# UI.net
KiCad netlist of a schematic drawn in Altium Designer
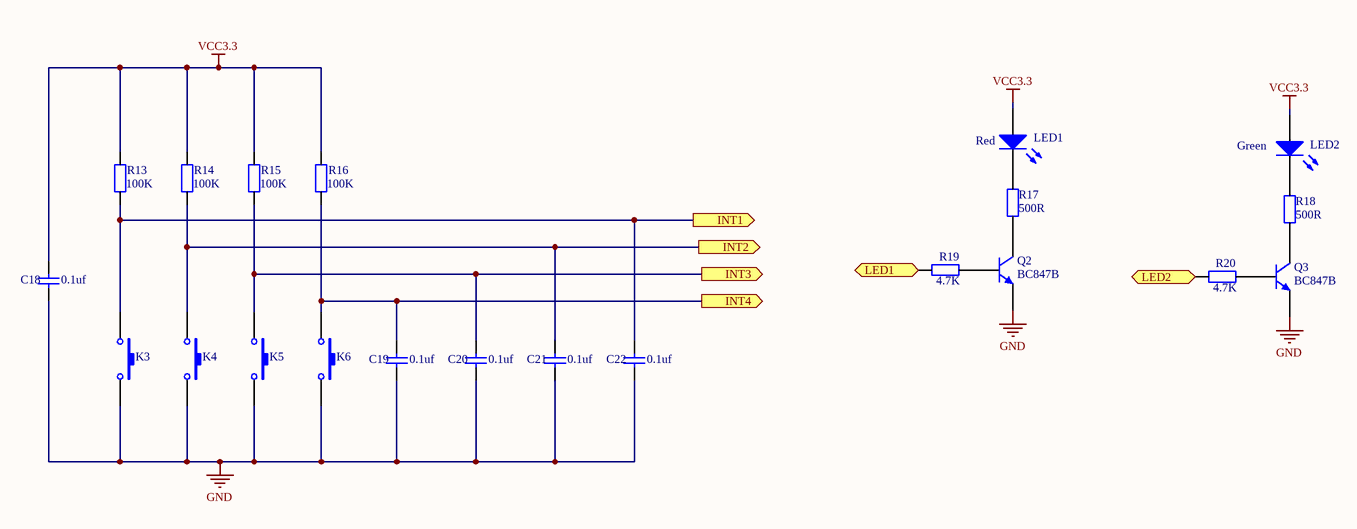
[diagram p0: UI.SchDoc]

(export (version "E")
  (design (tool "Eeschema 10.0.6"))
  (components
    (comp (ref "C18")
      (value "0.1uf")
      (footprint "0603")
      (fields (field (name "Comment") "Capacitor-0603"))
      (libsource (lib "原理图库") (part "Capacitor-0603"))
    )
    (comp (ref "C19")
      (value "0.1uf")
      (footprint "0603")
      (fields (field (name "Comment") "Capacitor-0603"))
      (libsource (lib "原理图库") (part "Capacitor-0603"))
    )
    (comp (ref "C20")
      (value "0.1uf")
      (footprint "0603")
      (fields (field (name "Comment") "Capacitor-0603"))
      (libsource (lib "原理图库") (part "Capacitor-0603"))
    )
    (comp (ref "C21")
      (value "0.1uf")
      (footprint "0603")
      (fields (field (name "Comment") "Capacitor-0603"))
      (libsource (lib "原理图库") (part "Capacitor-0603"))
    )
    (comp (ref "C22")
      (value "0.1uf")
      (footprint "0603")
      (fields (field (name "Comment") "Capacitor-0603"))
      (libsource (lib "原理图库") (part "Capacitor-0603"))
    )
    (comp (ref "K3") (value "按键") (footprint "mini按键") (libsource (lib "原理图库") (part "按键")))
    (comp (ref "K4") (value "按键") (footprint "mini按键") (libsource (lib "原理图库") (part "按键")))
    (comp (ref "K5") (value "按键") (footprint "mini按键") (libsource (lib "原理图库") (part "按键")))
    (comp (ref "K6") (value "按键") (footprint "mini按键") (libsource (lib "原理图库") (part "按键")))
    (comp (ref "LED1")
      (value "LED")
      (footprint "外插小灯")
      (fields (field (name "COLOR") "Red"))
      (libsource (lib "原理图库") (part "LED"))
    )
    (comp (ref "LED2")
      (value "LED")
      (footprint "外插小灯")
      (fields (field (name "COLOR") "Green"))
      (libsource (lib "原理图库") (part "LED"))
    )
    (comp (ref "Q2")
      (value "BC847")
      (footprint "BC847B")
      (fields (field (name "NAME") "BC847B"))
      (libsource (lib "原理图库") (part "BC847"))
    )
    (comp (ref "Q3")
      (value "BC847")
      (footprint "BC847B")
      (fields (field (name "NAME") "BC847B"))
      (libsource (lib "原理图库") (part "BC847"))
    )
    (comp (ref "R13")
      (value "100K")
      (footprint "0603")
      (fields (field (name "Comment") "Resistor-0603"))
      (libsource (lib "原理图库") (part "Resistor-0603"))
    )
    (comp (ref "R14")
      (value "100K")
      (footprint "0603")
      (fields (field (name "Comment") "Resistor-0603"))
      (libsource (lib "原理图库") (part "Resistor-0603"))
    )
    (comp (ref "R15")
      (value "100K")
      (footprint "0603")
      (fields (field (name "Comment") "Resistor-0603"))
      (libsource (lib "原理图库") (part "Resistor-0603"))
    )
    (comp (ref "R16")
      (value "100K")
      (footprint "0603")
      (fields (field (name "Comment") "Resistor-0603"))
      (libsource (lib "原理图库") (part "Resistor-0603"))
    )
    (comp (ref "R17")
      (value "500R")
      (footprint "0603")
      (fields (field (name "Comment") "Resistor-0603"))
      (libsource (lib "原理图库") (part "Resistor-0603"))
    )
    (comp (ref "R18")
      (value "500R")
      (footprint "0603")
      (fields (field (name "Comment") "Resistor-0603"))
      (libsource (lib "原理图库") (part "Resistor-0603"))
    )
    (comp (ref "R19")
      (value "4.7K")
      (footprint "0603")
      (fields (field (name "Comment") "Resistor-0603"))
      (libsource (lib "") (part "Resistor-0603_1"))
    )
    (comp (ref "R20")
      (value "4.7K")
      (footprint "0603")
      (fields (field (name "Comment") "Resistor-0603"))
      (libsource (lib "") (part "Resistor-0603_1"))
    )
  )
  (nets
    (net (code "1") (name "/INT1") (class "Default")
      (node (ref "C22") (pin "2") (pinfunction "2_2") (pintype "passive"))
      (node (ref "K3") (pin "1") (pinfunction "1_1") (pintype "passive"))
      (node (ref "R13") (pin "1") (pinfunction "1_1") (pintype "passive"))
    )
    (net (code "2") (name "/INT2") (class "Default")
      (node (ref "C21") (pin "2") (pinfunction "2_2") (pintype "passive"))
      (node (ref "K4") (pin "1") (pinfunction "1_1") (pintype "passive"))
      (node (ref "R14") (pin "1") (pinfunction "1_1") (pintype "passive"))
    )
    (net (code "3") (name "/INT3") (class "Default")
      (node (ref "C20") (pin "2") (pinfunction "2_2") (pintype "passive"))
      (node (ref "K5") (pin "1") (pinfunction "1_1") (pintype "passive"))
      (node (ref "R15") (pin "1") (pinfunction "1_1") (pintype "passive"))
    )
    (net (code "4") (name "/INT4") (class "Default")
      (node (ref "C19") (pin "2") (pinfunction "2_2") (pintype "passive"))
      (node (ref "K6") (pin "1") (pinfunction "1_1") (pintype "passive"))
      (node (ref "R16") (pin "1") (pinfunction "1_1") (pintype "passive"))
    )
    (net (code "5") (name "/LED1") (class "Default")
      (node (ref "R19") (pin "2") (pinfunction "2_2") (pintype "passive"))
    )
    (net (code "6") (name "/LED2") (class "Default")
      (node (ref "R20") (pin "2") (pinfunction "2_2") (pintype "passive"))
    )
    (net (code "7") (name "GND") (class "Default")
      (node (ref "C18") (pin "1") (pinfunction "1_1") (pintype "passive"))
      (node (ref "C19") (pin "1") (pinfunction "1_1") (pintype "passive"))
      (node (ref "C20") (pin "1") (pinfunction "1_1") (pintype "passive"))
      (node (ref "C21") (pin "1") (pinfunction "1_1") (pintype "passive"))
      (node (ref "C22") (pin "1") (pinfunction "1_1") (pintype "passive"))
      (node (ref "K3") (pin "2") (pinfunction "2_2") (pintype "passive"))
      (node (ref "K4") (pin "2") (pinfunction "2_2") (pintype "passive"))
      (node (ref "K5") (pin "2") (pinfunction "2_2") (pintype "passive"))
      (node (ref "K6") (pin "2") (pinfunction "2_2") (pintype "passive"))
      (node (ref "Q2") (pin "1") (pinfunction "E_1") (pintype "passive"))
      (node (ref "Q3") (pin "1") (pinfunction "E_1") (pintype "passive"))
    )
    (net (code "8") (name "Net-(LED1-Pad2)") (class "Default")
      (node (ref "LED1") (pin "2") (pinfunction "2_2") (pintype "passive"))
      (node (ref "R17") (pin "2") (pinfunction "2_2") (pintype "passive"))
    )
    (net (code "9") (name "Net-(LED2-Pad2)") (class "Default")
      (node (ref "LED2") (pin "2") (pinfunction "2_2") (pintype "passive"))
      (node (ref "R18") (pin "2") (pinfunction "2_2") (pintype "passive"))
    )
    (net (code "10") (name "Net-(Q2-B)") (class "Default")
      (node (ref "Q2") (pin "2") (pinfunction "B_2") (pintype "passive"))
      (node (ref "R19") (pin "1") (pinfunction "1_1") (pintype "passive"))
    )
    (net (code "11") (name "Net-(Q2-C)") (class "Default")
      (node (ref "Q2") (pin "3") (pinfunction "C_3") (pintype "passive"))
      (node (ref "R17") (pin "1") (pinfunction "1_1") (pintype "passive"))
    )
    (net (code "12") (name "Net-(Q3-B)") (class "Default")
      (node (ref "Q3") (pin "2") (pinfunction "B_2") (pintype "passive"))
      (node (ref "R20") (pin "1") (pinfunction "1_1") (pintype "passive"))
    )
    (net (code "13") (name "Net-(Q3-C)") (class "Default")
      (node (ref "Q3") (pin "3") (pinfunction "C_3") (pintype "passive"))
      (node (ref "R18") (pin "1") (pinfunction "1_1") (pintype "passive"))
    )
    (net (code "14") (name "VCC3.3") (class "Default")
      (node (ref "C18") (pin "2") (pinfunction "2_2") (pintype "passive"))
      (node (ref "LED1") (pin "1") (pinfunction "A_1") (pintype "passive"))
      (node (ref "LED2") (pin "1") (pinfunction "A_1") (pintype "passive"))
      (node (ref "R13") (pin "2") (pinfunction "2_2") (pintype "passive"))
      (node (ref "R14") (pin "2") (pinfunction "2_2") (pintype "passive"))
      (node (ref "R15") (pin "2") (pinfunction "2_2") (pintype "passive"))
      (node (ref "R16") (pin "2") (pinfunction "2_2") (pintype "passive"))
    )
  )
)
